# SCH1.net
KiCad netlist of a schematic drawn in EAGLE
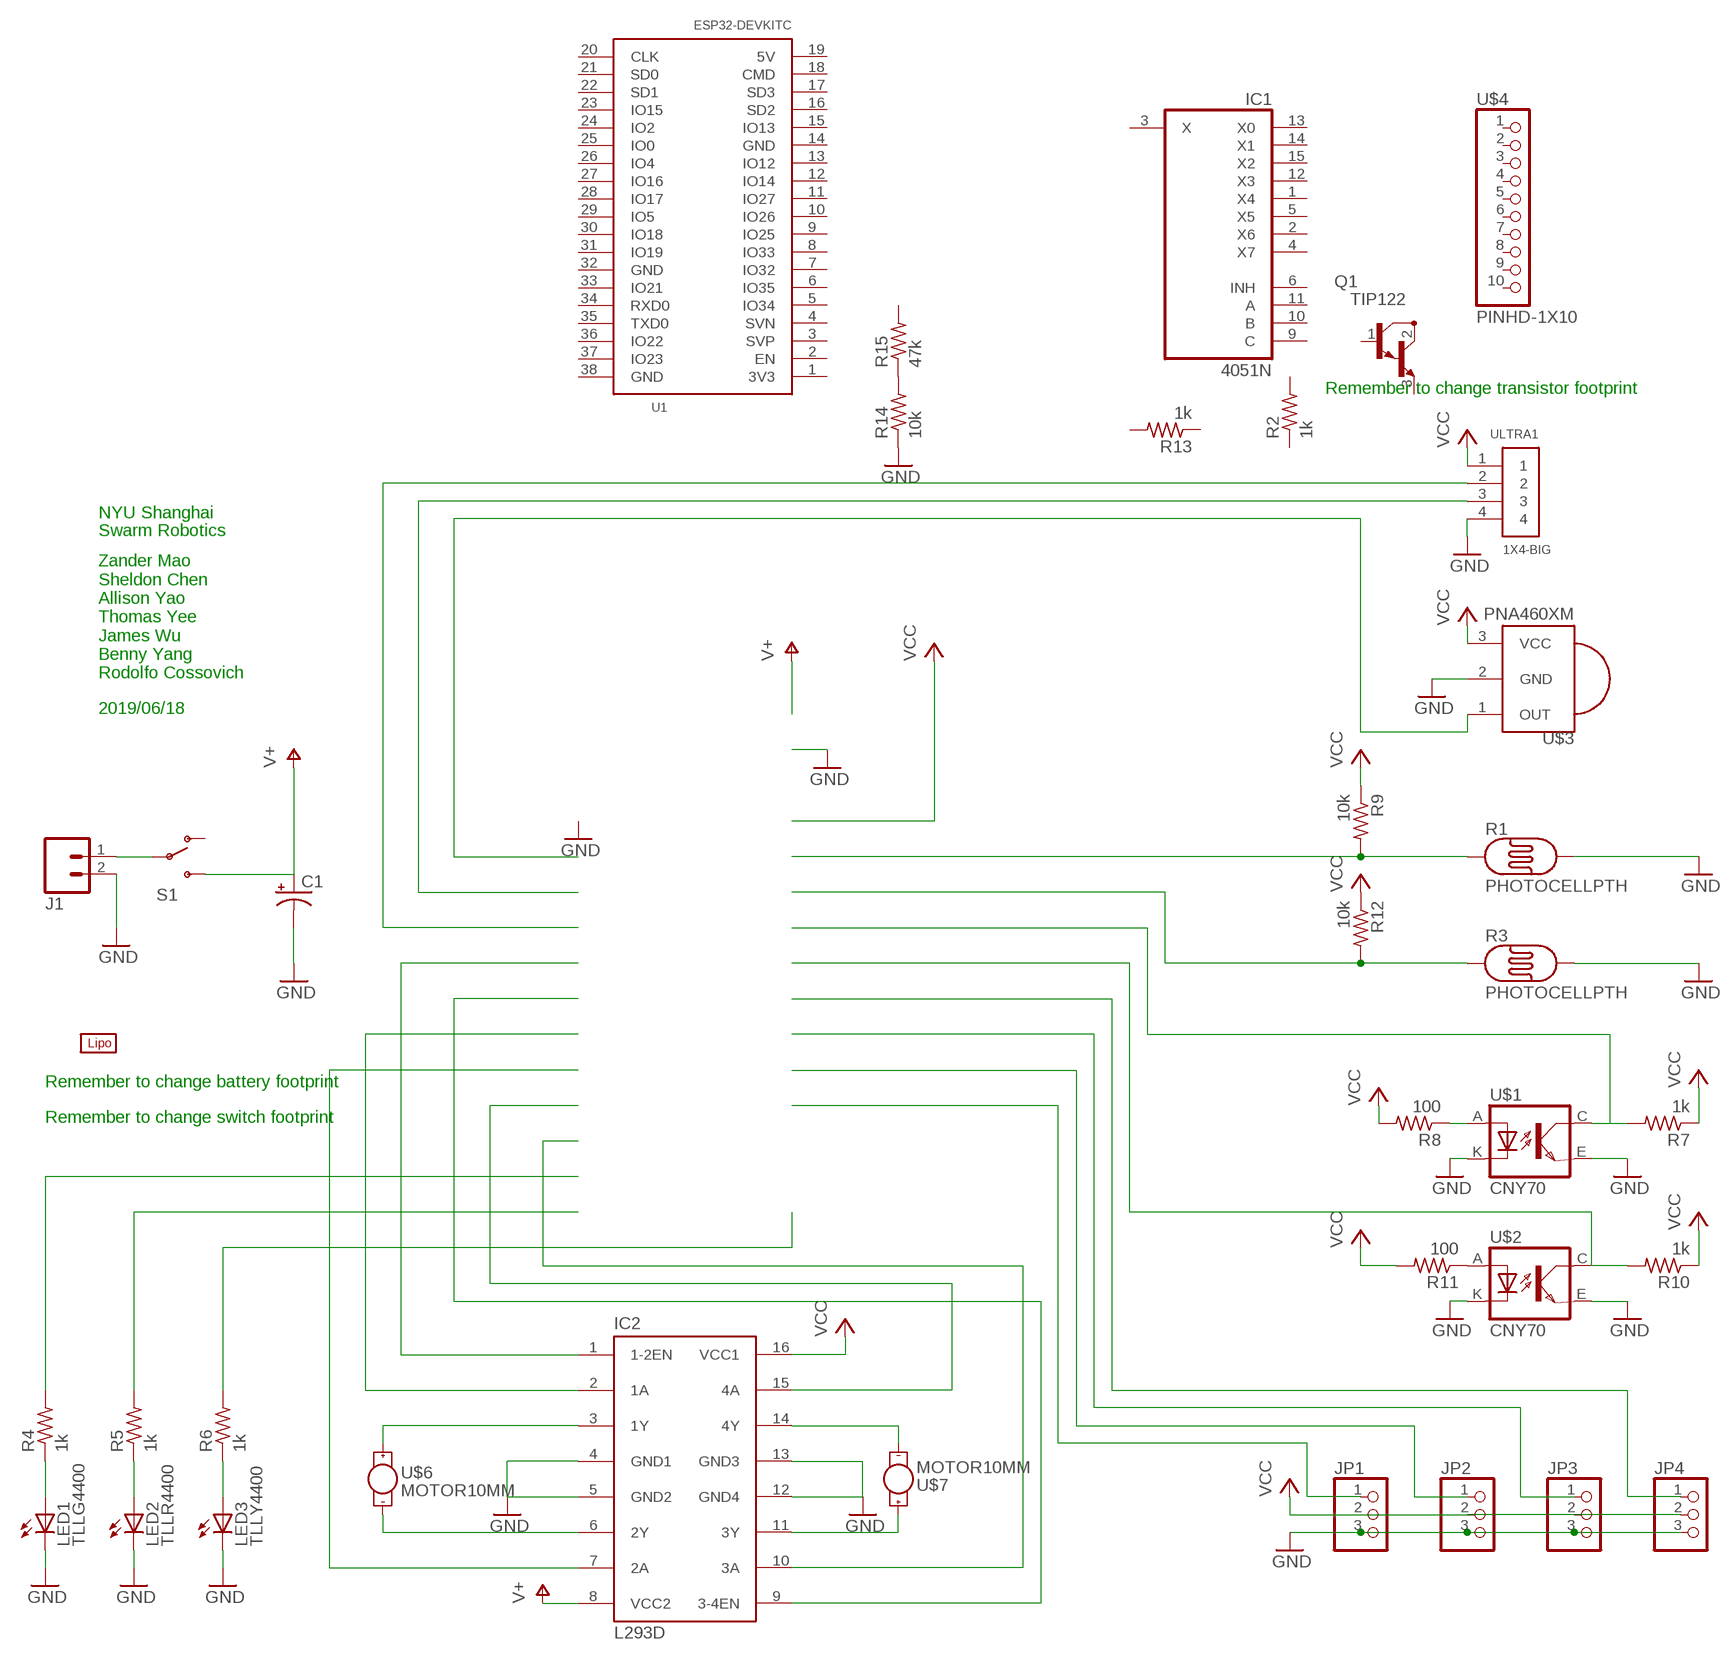
[diagram p0: schematic, sheet 1]

(export (version "E")
  (design (tool "Eeschema 10.0.6"))
  (components
    (comp (ref "C1")
      (value "CPOL-USE10-20")
      (footprint "eagle-import:EB20D")
      (libsource (lib "eagle-import") (part "CPOL-USE10-20"))
    )
    (comp (ref "IC1")
      (value "4051N")
      (footprint "eagle-import:DIL16")
      (libsource (lib "eagle-import") (part "4051N"))
    )
    (comp (ref "IC2")
      (value "L293D")
      (footprint "eagle-import:DIL16")
      (libsource (lib "eagle-import") (part "L293D"))
    )
    (comp (ref "J1")
      (value "M02-JST-2-PTH-NO_SILK")
      (footprint "eagle-import:JST-2-PTH-NS")
      (libsource (lib "eagle-import") (part "M02-JST-2-PTH-NO_SILK"))
    )
    (comp (ref "JP1")
      (value "PINHD-1X3")
      (footprint "eagle-import:1X03")
      (libsource (lib "eagle-import") (part "PINHD-1X3"))
    )
    (comp (ref "JP2")
      (value "PINHD-1X3")
      (footprint "eagle-import:1X03")
      (libsource (lib "eagle-import") (part "PINHD-1X3"))
    )
    (comp (ref "JP3")
      (value "PINHD-1X3")
      (footprint "eagle-import:1X03")
      (libsource (lib "eagle-import") (part "PINHD-1X3"))
    )
    (comp (ref "JP4")
      (value "PINHD-1X3")
      (footprint "eagle-import:1X03")
      (libsource (lib "eagle-import") (part "PINHD-1X3"))
    )
    (comp (ref "LED1")
      (value "TLLG4400")
      (footprint "eagle-import:LED3MM")
      (fields (field (name "MF") "VISHAY SEMICONDUCTOR"))
      (libsource (lib "eagle-import") (part "TLLG4400"))
    )
    (comp (ref "LED2")
      (value "TLLR4400")
      (footprint "eagle-import:LED3MM")
      (fields (field (name "MF") "VISHAY SEMICONDUCTOR"))
      (libsource (lib "eagle-import") (part "TLLR4400"))
    )
    (comp (ref "LED3")
      (value "TLLY4400")
      (footprint "eagle-import:LED3MM")
      (fields (field (name "MF") "VISHAY SEMICONDUCTOR"))
      (libsource (lib "eagle-import") (part "TLLY4400"))
    )
    (comp (ref "Q1")
      (value "TIP122")
      (footprint "eagle-import:TO220")
      (libsource (lib "eagle-import") (part "TIP122"))
    )
    (comp (ref "R1")
      (value "PHOTOCELLPTH")
      (footprint "eagle-import:PHOTOCELL")
      (libsource (lib "eagle-import") (part "PHOTOCELLPTH"))
    )
    (comp (ref "R2")
      (value "1k")
      (footprint "eagle-import:0207_12")
      (libsource (lib "eagle-import") (part "R-US_0207/12"))
    )
    (comp (ref "R3")
      (value "PHOTOCELLPTH")
      (footprint "eagle-import:PHOTOCELL")
      (libsource (lib "eagle-import") (part "PHOTOCELLPTH"))
    )
    (comp (ref "R4")
      (value "1k")
      (footprint "eagle-import:0207_12")
      (libsource (lib "eagle-import") (part "R-US_0207/12"))
    )
    (comp (ref "R5")
      (value "1k")
      (footprint "eagle-import:0207_12")
      (libsource (lib "eagle-import") (part "R-US_0207/12"))
    )
    (comp (ref "R6")
      (value "1k")
      (footprint "eagle-import:0207_12")
      (libsource (lib "eagle-import") (part "R-US_0207/12"))
    )
    (comp (ref "R7")
      (value "1k")
      (footprint "eagle-import:0207_12")
      (libsource (lib "eagle-import") (part "R-US_0207/12"))
    )
    (comp (ref "R8")
      (value "100")
      (footprint "eagle-import:0207_12")
      (libsource (lib "eagle-import") (part "R-US_0207/12"))
    )
    (comp (ref "R9")
      (value "10k")
      (footprint "eagle-import:0207_12")
      (libsource (lib "eagle-import") (part "R-US_0207/12"))
    )
    (comp (ref "R10")
      (value "1k")
      (footprint "eagle-import:0207_12")
      (libsource (lib "eagle-import") (part "R-US_0207/12"))
    )
    (comp (ref "R11")
      (value "100")
      (footprint "eagle-import:0207_12")
      (libsource (lib "eagle-import") (part "R-US_0207/12"))
    )
    (comp (ref "R12")
      (value "10k")
      (footprint "eagle-import:0207_12")
      (libsource (lib "eagle-import") (part "R-US_0207/12"))
    )
    (comp (ref "R13")
      (value "1k")
      (footprint "eagle-import:0207_12")
      (libsource (lib "eagle-import") (part "R-US_0207/12"))
    )
    (comp (ref "R14")
      (value "10k")
      (footprint "eagle-import:0207_12")
      (libsource (lib "eagle-import") (part "R-US_0207/12"))
    )
    (comp (ref "R15")
      (value "47k")
      (footprint "eagle-import:0207_12")
      (libsource (lib "eagle-import") (part "R-US_0207/12"))
    )
    (comp (ref "S1")
      (value "SWITCH-SPDTPTH2")
      (footprint "eagle-import:SWITCHE-DPDT")
      (libsource (lib "eagle-import") (part "SWITCH-SPDTPTH2"))
    )
    (comp (ref "U$1")
      (value "CNY70")
      (footprint "eagle-import:4")
      (libsource (lib "eagle-import") (part "CNY70"))
    )
    (comp (ref "U$2")
      (value "CNY70")
      (footprint "eagle-import:4")
      (libsource (lib "eagle-import") (part "CNY70"))
    )
    (comp (ref "U$3")
      (value "PNA460XM")
      (footprint "eagle-import:PNA460XM")
      (libsource (lib "eagle-import") (part "PNA460XM"))
    )
    (comp (ref "U$4")
      (value "PINHD-1X10")
      (footprint "eagle-import:1X10-BIG")
      (libsource (lib "eagle-import") (part "PINHD-1X10"))
    )
    (comp (ref "U$5")
      (value "LIPO-OUTLINE2000")
      (footprint "eagle-import:LIPO-2000")
      (libsource (lib "eagle-import") (part "LIPO-OUTLINE2000"))
    )
    (comp (ref "U$6")
      (value "MOTOR10MM")
      (footprint "eagle-import:VIBE-MOTOR-10MM")
      (libsource (lib "eagle-import") (part "MOTOR10MM"))
    )
    (comp (ref "U$7")
      (value "MOTOR10MM")
      (footprint "eagle-import:VIBE-MOTOR-10MM")
      (libsource (lib "eagle-import") (part "MOTOR10MM"))
    )
    (comp (ref "U1")
      (value "ESP32DEVKITC")
      (footprint "eagle-import:ESP32-DEVKITC")
      (libsource (lib "eagle-import") (part "ESP32DEVKITC"))
    )
    (comp (ref "ULTRA1")
      (value "1X4-BIG")
      (footprint "eagle-import:1X04-BIG")
      (libsource (lib "eagle-import") (part "1X4-BIG"))
    )
  )
  (nets
    (net (code "1") (name "GND") (class "Default")
      (node (ref "C1") (pin "-") (pinfunction "-_-") (pintype "passive"))
      (node (ref "IC2") (pin "12") (pinfunction "GND4_12") (pintype "power_in"))
      (node (ref "IC2") (pin "13") (pinfunction "GND3_13") (pintype "power_in"))
      (node (ref "IC2") (pin "4") (pinfunction "GND1_4") (pintype "power_in"))
      (node (ref "IC2") (pin "5") (pinfunction "GND2_5") (pintype "power_in"))
      (node (ref "J1") (pin "2") (pinfunction "2_2") (pintype "passive"))
      (node (ref "JP1") (pin "3") (pinfunction "3_3") (pintype "passive"))
      (node (ref "JP2") (pin "3") (pinfunction "3_3") (pintype "passive"))
      (node (ref "JP3") (pin "3") (pinfunction "3_3") (pintype "passive"))
      (node (ref "JP4") (pin "3") (pinfunction "3_3") (pintype "passive"))
      (node (ref "LED1") (pin "K") (pinfunction "C_K") (pintype "passive"))
      (node (ref "LED2") (pin "K") (pinfunction "C_K") (pintype "passive"))
      (node (ref "LED3") (pin "K") (pinfunction "C_K") (pintype "passive"))
      (node (ref "R1") (pin "2") (pinfunction "P$2_2") (pintype "bidirectional"))
      (node (ref "R14") (pin "1") (pinfunction "1_1") (pintype "passive"))
      (node (ref "R3") (pin "2") (pinfunction "P$2_2") (pintype "bidirectional"))
      (node (ref "U$1") (pin "E") (pinfunction "EMI_E") (pintype "passive"))
      (node (ref "U$1") (pin "K") (pinfunction "C_K") (pintype "passive"))
      (node (ref "U$2") (pin "E") (pinfunction "EMI_E") (pintype "passive"))
      (node (ref "U$2") (pin "K") (pinfunction "C_K") (pintype "passive"))
      (node (ref "U$3") (pin "2") (pinfunction "GND_2") (pintype "power_in"))
      (node (ref "ULTRA1") (pin "4") (pinfunction "4_4") (pintype "bidirectional"))
    )
    (net (code "2") (name "Net-(IC2-1Y)") (class "Default")
      (node (ref "IC2") (pin "3") (pinfunction "1Y_3") (pintype "output"))
      (node (ref "U$6") (pin "+") (pinfunction "+_+") (pintype "bidirectional"))
    )
    (net (code "3") (name "Net-(IC2-2Y)") (class "Default")
      (node (ref "IC2") (pin "6") (pinfunction "2Y_6") (pintype "output"))
      (node (ref "U$6") (pin "-") (pinfunction "-_-") (pintype "bidirectional"))
    )
    (net (code "4") (name "Net-(IC2-3Y)") (class "Default")
      (node (ref "IC2") (pin "11") (pinfunction "3Y_11") (pintype "output"))
      (node (ref "U$7") (pin "+") (pinfunction "+_+") (pintype "bidirectional"))
    )
    (net (code "5") (name "Net-(IC2-4Y)") (class "Default")
      (node (ref "IC2") (pin "14") (pinfunction "4Y_14") (pintype "output"))
      (node (ref "U$7") (pin "-") (pinfunction "-_-") (pintype "bidirectional"))
    )
    (net (code "6") (name "Net-(LED1-PadA)") (class "Default")
      (node (ref "LED1") (pin "A") (pinfunction "A_A") (pintype "passive"))
      (node (ref "R4") (pin "1") (pinfunction "1_1") (pintype "passive"))
    )
    (net (code "7") (name "Net-(LED2-PadA)") (class "Default")
      (node (ref "LED2") (pin "A") (pinfunction "A_A") (pintype "passive"))
      (node (ref "R5") (pin "1") (pinfunction "1_1") (pintype "passive"))
    )
    (net (code "8") (name "Net-(LED3-PadA)") (class "Default")
      (node (ref "LED3") (pin "A") (pinfunction "A_A") (pintype "passive"))
      (node (ref "R6") (pin "1") (pinfunction "1_1") (pintype "passive"))
    )
    (net (code "9") (name "Net-(R1-P$1)") (class "Default")
      (node (ref "R1") (pin "1") (pinfunction "P$1_1") (pintype "bidirectional"))
      (node (ref "R9") (pin "2") (pinfunction "2_2") (pintype "passive"))
    )
    (net (code "10") (name "Net-(R3-P$1)") (class "Default")
      (node (ref "R12") (pin "2") (pinfunction "2_2") (pintype "passive"))
      (node (ref "R3") (pin "1") (pinfunction "P$1_1") (pintype "bidirectional"))
    )
    (net (code "11") (name "Net-(R8-Pad1)") (class "Default")
      (node (ref "R8") (pin "1") (pinfunction "1_1") (pintype "passive"))
      (node (ref "U$1") (pin "A") (pinfunction "A_A") (pintype "passive"))
    )
    (net (code "12") (name "Net-(R11-Pad1)") (class "Default")
      (node (ref "R11") (pin "1") (pinfunction "1_1") (pintype "passive"))
      (node (ref "U$2") (pin "A") (pinfunction "A_A") (pintype "passive"))
    )
    (net (code "13") (name "Net-(R14-Pad2)") (class "Default")
      (node (ref "R14") (pin "2") (pinfunction "2_2") (pintype "passive"))
      (node (ref "R15") (pin "1") (pinfunction "1_1") (pintype "passive"))
    )
    (net (code "14") (name "Net-(S1-P)") (class "Default")
      (node (ref "J1") (pin "1") (pinfunction "1_1") (pintype "passive"))
      (node (ref "S1") (pin "2") (pinfunction "P_2") (pintype "passive"))
    )
    (net (code "15") (name "Net-(U$1-COL)") (class "Default")
      (node (ref "R7") (pin "2") (pinfunction "2_2") (pintype "passive"))
      (node (ref "U$1") (pin "C") (pinfunction "COL_C") (pintype "passive"))
    )
    (net (code "16") (name "Net-(U$2-COL)") (class "Default")
      (node (ref "R10") (pin "2") (pinfunction "2_2") (pintype "passive"))
      (node (ref "U$2") (pin "C") (pinfunction "COL_C") (pintype "passive"))
    )
    (net (code "17") (name "V+") (class "Default")
      (node (ref "C1") (pin "+") (pinfunction "+_+") (pintype "passive"))
      (node (ref "IC2") (pin "8") (pinfunction "VCC2_8") (pintype "power_in"))
      (node (ref "S1") (pin "3") (pinfunction "S_3") (pintype "passive"))
    )
    (net (code "18") (name "VCC") (class "Default")
      (node (ref "IC2") (pin "16") (pinfunction "VCC1_16") (pintype "power_in"))
      (node (ref "JP1") (pin "2") (pinfunction "2_2") (pintype "passive"))
      (node (ref "JP2") (pin "2") (pinfunction "2_2") (pintype "passive"))
      (node (ref "JP3") (pin "2") (pinfunction "2_2") (pintype "passive"))
      (node (ref "JP4") (pin "2") (pinfunction "2_2") (pintype "passive"))
      (node (ref "R10") (pin "1") (pinfunction "1_1") (pintype "passive"))
      (node (ref "R11") (pin "2") (pinfunction "2_2") (pintype "passive"))
      (node (ref "R12") (pin "1") (pinfunction "1_1") (pintype "passive"))
      (node (ref "R7") (pin "1") (pinfunction "1_1") (pintype "passive"))
      (node (ref "R8") (pin "2") (pinfunction "2_2") (pintype "passive"))
      (node (ref "R9") (pin "1") (pinfunction "1_1") (pintype "passive"))
      (node (ref "U$3") (pin "3") (pinfunction "VCC_3") (pintype "power_in"))
      (node (ref "ULTRA1") (pin "1") (pinfunction "1_1") (pintype "bidirectional"))
    )
    (net (code "19") (name "unconnected-(IC1A-A-Pad11)") (class "Default")
      (node (ref "IC1") (pin "11") (pinfunction "A_11") (pintype "input"))
    )
    (net (code "20") (name "unconnected-(IC1A-B-Pad10)") (class "Default")
      (node (ref "IC1") (pin "10") (pinfunction "B_10") (pintype "input"))
    )
    (net (code "21") (name "unconnected-(IC1A-C-Pad9)") (class "Default")
      (node (ref "IC1") (pin "9") (pinfunction "C_9") (pintype "input"))
    )
    (net (code "22") (name "unconnected-(IC1A-INH-Pad6)") (class "Default")
      (node (ref "IC1") (pin "6") (pinfunction "INH_6") (pintype "input"))
    )
    (net (code "23") (name "unconnected-(IC1A-X-Pad3)") (class "Default")
      (node (ref "IC1") (pin "3") (pinfunction "X_3") (pintype "bidirectional"))
    )
    (net (code "24") (name "unconnected-(IC1A-X0-Pad13)") (class "Default")
      (node (ref "IC1") (pin "13") (pinfunction "X0_13") (pintype "bidirectional"))
    )
    (net (code "25") (name "unconnected-(IC1A-X1-Pad14)") (class "Default")
      (node (ref "IC1") (pin "14") (pinfunction "X1_14") (pintype "bidirectional"))
    )
    (net (code "26") (name "unconnected-(IC1A-X2-Pad15)") (class "Default")
      (node (ref "IC1") (pin "15") (pinfunction "X2_15") (pintype "bidirectional"))
    )
    (net (code "27") (name "unconnected-(IC1A-X3-Pad12)") (class "Default")
      (node (ref "IC1") (pin "12") (pinfunction "X3_12") (pintype "bidirectional"))
    )
    (net (code "28") (name "unconnected-(IC1A-X4-Pad1)") (class "Default")
      (node (ref "IC1") (pin "1") (pinfunction "X4_1") (pintype "bidirectional"))
    )
    (net (code "29") (name "unconnected-(IC1A-X5-Pad5)") (class "Default")
      (node (ref "IC1") (pin "5") (pinfunction "X5_5") (pintype "bidirectional"))
    )
    (net (code "30") (name "unconnected-(IC1A-X6-Pad2)") (class "Default")
      (node (ref "IC1") (pin "2") (pinfunction "X6_2") (pintype "bidirectional"))
    )
    (net (code "31") (name "unconnected-(IC1A-X7-Pad4)") (class "Default")
      (node (ref "IC1") (pin "4") (pinfunction "X7_4") (pintype "bidirectional"))
    )
    (net (code "32") (name "unconnected-(IC2-1-2EN-Pad1)") (class "Default")
      (node (ref "IC2") (pin "1") (pinfunction "1-2EN_1") (pintype "input"))
    )
    (net (code "33") (name "unconnected-(IC2-1A-Pad2)") (class "Default")
      (node (ref "IC2") (pin "2") (pinfunction "1A_2") (pintype "input"))
    )
    (net (code "34") (name "unconnected-(IC2-2A-Pad7)") (class "Default")
      (node (ref "IC2") (pin "7") (pinfunction "2A_7") (pintype "input"))
    )
    (net (code "35") (name "unconnected-(IC2-3-4EN-Pad9)") (class "Default")
      (node (ref "IC2") (pin "9") (pinfunction "3-4EN_9") (pintype "input"))
    )
    (net (code "36") (name "unconnected-(IC2-3A-Pad10)") (class "Default")
      (node (ref "IC2") (pin "10") (pinfunction "3A_10") (pintype "input"))
    )
    (net (code "37") (name "unconnected-(IC2-4A-Pad15)") (class "Default")
      (node (ref "IC2") (pin "15") (pinfunction "4A_15") (pintype "input"))
    )
    (net (code "38") (name "unconnected-(JP1-Pad1)") (class "Default")
      (node (ref "JP1") (pin "1") (pinfunction "1_1") (pintype "passive"))
    )
    (net (code "39") (name "unconnected-(JP2-Pad1)") (class "Default")
      (node (ref "JP2") (pin "1") (pinfunction "1_1") (pintype "passive"))
    )
    (net (code "40") (name "unconnected-(JP3-Pad1)") (class "Default")
      (node (ref "JP3") (pin "1") (pinfunction "1_1") (pintype "passive"))
    )
    (net (code "41") (name "unconnected-(JP4-Pad1)") (class "Default")
      (node (ref "JP4") (pin "1") (pinfunction "1_1") (pintype "passive"))
    )
    (net (code "42") (name "unconnected-(Q1-B-Pad1)") (class "Default")
      (node (ref "Q1") (pin "1") (pinfunction "B_1") (pintype "passive"))
    )
    (net (code "43") (name "unconnected-(Q1-C-Pad2)") (class "Default")
      (node (ref "Q1") (pin "2") (pinfunction "C_2") (pintype "passive"))
    )
    (net (code "44") (name "unconnected-(Q1-E-Pad3)") (class "Default")
      (node (ref "Q1") (pin "3") (pinfunction "E_3") (pintype "passive"))
    )
    (net (code "45") (name "unconnected-(R2-Pad1)") (class "Default")
      (node (ref "R2") (pin "1") (pinfunction "1_1") (pintype "passive"))
    )
    (net (code "46") (name "unconnected-(R2-Pad2)") (class "Default")
      (node (ref "R2") (pin "2") (pinfunction "2_2") (pintype "passive"))
    )
    (net (code "47") (name "unconnected-(R4-Pad2)") (class "Default")
      (node (ref "R4") (pin "2") (pinfunction "2_2") (pintype "passive"))
    )
    (net (code "48") (name "unconnected-(R5-Pad2)") (class "Default")
      (node (ref "R5") (pin "2") (pinfunction "2_2") (pintype "passive"))
    )
    (net (code "49") (name "unconnected-(R6-Pad2)") (class "Default")
      (node (ref "R6") (pin "2") (pinfunction "2_2") (pintype "passive"))
    )
    (net (code "50") (name "unconnected-(R13-Pad1)") (class "Default")
      (node (ref "R13") (pin "1") (pinfunction "1_1") (pintype "passive"))
    )
    (net (code "51") (name "unconnected-(R13-Pad2)") (class "Default")
      (node (ref "R13") (pin "2") (pinfunction "2_2") (pintype "passive"))
    )
    (net (code "52") (name "unconnected-(R15-Pad2)") (class "Default")
      (node (ref "R15") (pin "2") (pinfunction "2_2") (pintype "passive"))
    )
    (net (code "53") (name "unconnected-(S1-O-Pad1)") (class "Default")
      (node (ref "S1") (pin "1") (pinfunction "O_1") (pintype "passive"))
    )
    (net (code "54") (name "unconnected-(U$3-OUT-Pad1)") (class "Default")
      (node (ref "U$3") (pin "1") (pinfunction "OUT_1") (pintype "output"))
    )
    (net (code "55") (name "unconnected-(U$4-Pad1)") (class "Default")
      (node (ref "U$4") (pin "1") (pinfunction "1_1") (pintype "passive"))
    )
    (net (code "56") (name "unconnected-(U$4-Pad2)") (class "Default")
      (node (ref "U$4") (pin "2") (pinfunction "2_2") (pintype "passive"))
    )
    (net (code "57") (name "unconnected-(U$4-Pad3)") (class "Default")
      (node (ref "U$4") (pin "3") (pinfunction "3_3") (pintype "passive"))
    )
    (net (code "58") (name "unconnected-(U$4-Pad4)") (class "Default")
      (node (ref "U$4") (pin "4") (pinfunction "4_4") (pintype "passive"))
    )
    (net (code "59") (name "unconnected-(U$4-Pad5)") (class "Default")
      (node (ref "U$4") (pin "5") (pinfunction "5_5") (pintype "passive"))
    )
    (net (code "60") (name "unconnected-(U$4-Pad6)") (class "Default")
      (node (ref "U$4") (pin "6") (pinfunction "6_6") (pintype "passive"))
    )
    (net (code "61") (name "unconnected-(U$4-Pad7)") (class "Default")
      (node (ref "U$4") (pin "7") (pinfunction "7_7") (pintype "passive"))
    )
    (net (code "62") (name "unconnected-(U$4-Pad8)") (class "Default")
      (node (ref "U$4") (pin "8") (pinfunction "8_8") (pintype "passive"))
    )
    (net (code "63") (name "unconnected-(U$4-Pad9)") (class "Default")
      (node (ref "U$4") (pin "9") (pinfunction "9_9") (pintype "passive"))
    )
    (net (code "64") (name "unconnected-(U$4-Pad10)") (class "Default")
      (node (ref "U$4") (pin "10") (pinfunction "10_10") (pintype "passive"))
    )
    (net (code "65") (name "unconnected-(U1-3V3-Pad1)") (class "Default")
      (node (ref "U1") (pin "1") (pinfunction "3V3_1") (pintype "bidirectional"))
    )
    (net (code "66") (name "unconnected-(U1-5V-Pad19)") (class "Default")
      (node (ref "U1") (pin "19") (pinfunction "5V_19") (pintype "bidirectional"))
    )
    (net (code "67") (name "unconnected-(U1-CLK-Pad20)") (class "Default")
      (node (ref "U1") (pin "20") (pinfunction "CLK_20") (pintype "bidirectional"))
    )
    (net (code "68") (name "unconnected-(U1-CMD-Pad18)") (class "Default")
      (node (ref "U1") (pin "18") (pinfunction "CMD_18") (pintype "bidirectional"))
    )
    (net (code "69") (name "unconnected-(U1-EN-Pad2)") (class "Default")
      (node (ref "U1") (pin "2") (pinfunction "EN_2") (pintype "bidirectional"))
    )
    (net (code "70") (name "unconnected-(U1-GND-Pad14)") (class "Default")
      (node (ref "U1") (pin "14") (pinfunction "GND_14") (pintype "bidirectional"))
    )
    (net (code "71") (name "unconnected-(U1-GND-Pad32)") (class "Default")
      (node (ref "U1") (pin "32") (pinfunction "GND_32") (pintype "bidirectional"))
    )
    (net (code "72") (name "unconnected-(U1-GND-Pad38)") (class "Default")
      (node (ref "U1") (pin "38") (pinfunction "GND_38") (pintype "bidirectional"))
    )
    (net (code "73") (name "unconnected-(U1-IO0-Pad25)") (class "Default")
      (node (ref "U1") (pin "25") (pinfunction "IO0_25") (pintype "bidirectional"))
    )
    (net (code "74") (name "unconnected-(U1-IO2-Pad24)") (class "Default")
      (node (ref "U1") (pin "24") (pinfunction "IO2_24") (pintype "bidirectional"))
    )
    (net (code "75") (name "unconnected-(U1-IO4-Pad26)") (class "Default")
      (node (ref "U1") (pin "26") (pinfunction "IO4_26") (pintype "bidirectional"))
    )
    (net (code "76") (name "unconnected-(U1-IO5-Pad29)") (class "Default")
      (node (ref "U1") (pin "29") (pinfunction "IO5_29") (pintype "bidirectional"))
    )
    (net (code "77") (name "unconnected-(U1-IO12-Pad13)") (class "Default")
      (node (ref "U1") (pin "13") (pinfunction "IO12_13") (pintype "bidirectional"))
    )
    (net (code "78") (name "unconnected-(U1-IO13-Pad15)") (class "Default")
      (node (ref "U1") (pin "15") (pinfunction "IO13_15") (pintype "bidirectional"))
    )
    (net (code "79") (name "unconnected-(U1-IO14-Pad12)") (class "Default")
      (node (ref "U1") (pin "12") (pinfunction "IO14_12") (pintype "bidirectional"))
    )
    (net (code "80") (name "unconnected-(U1-IO15-Pad23)") (class "Default")
      (node (ref "U1") (pin "23") (pinfunction "IO15_23") (pintype "bidirectional"))
    )
    (net (code "81") (name "unconnected-(U1-IO16-Pad27)") (class "Default")
      (node (ref "U1") (pin "27") (pinfunction "IO16_27") (pintype "bidirectional"))
    )
    (net (code "82") (name "unconnected-(U1-IO17-Pad28)") (class "Default")
      (node (ref "U1") (pin "28") (pinfunction "IO17_28") (pintype "bidirectional"))
    )
    (net (code "83") (name "unconnected-(U1-IO18-Pad30)") (class "Default")
      (node (ref "U1") (pin "30") (pinfunction "IO18_30") (pintype "bidirectional"))
    )
    (net (code "84") (name "unconnected-(U1-IO19-Pad31)") (class "Default")
      (node (ref "U1") (pin "31") (pinfunction "IO19_31") (pintype "bidirectional"))
    )
    (net (code "85") (name "unconnected-(U1-IO21-Pad33)") (class "Default")
      (node (ref "U1") (pin "33") (pinfunction "IO21_33") (pintype "bidirectional"))
    )
    (net (code "86") (name "unconnected-(U1-IO22-Pad36)") (class "Default")
      (node (ref "U1") (pin "36") (pinfunction "IO22_36") (pintype "bidirectional"))
    )
    (net (code "87") (name "unconnected-(U1-IO23-Pad37)") (class "Default")
      (node (ref "U1") (pin "37") (pinfunction "IO23_37") (pintype "bidirectional"))
    )
    (net (code "88") (name "unconnected-(U1-IO25-Pad9)") (class "Default")
      (node (ref "U1") (pin "9") (pinfunction "IO25_9") (pintype "bidirectional"))
    )
    (net (code "89") (name "unconnected-(U1-IO26-Pad10)") (class "Default")
      (node (ref "U1") (pin "10") (pinfunction "IO26_10") (pintype "bidirectional"))
    )
    (net (code "90") (name "unconnected-(U1-IO27-Pad11)") (class "Default")
      (node (ref "U1") (pin "11") (pinfunction "IO27_11") (pintype "bidirectional"))
    )
    (net (code "91") (name "unconnected-(U1-IO32-Pad7)") (class "Default")
      (node (ref "U1") (pin "7") (pinfunction "IO32_7") (pintype "bidirectional"))
    )
    (net (code "92") (name "unconnected-(U1-IO33-Pad8)") (class "Default")
      (node (ref "U1") (pin "8") (pinfunction "IO33_8") (pintype "bidirectional"))
    )
    (net (code "93") (name "unconnected-(U1-IO34-Pad5)") (class "Default")
      (node (ref "U1") (pin "5") (pinfunction "IO34_5") (pintype "bidirectional"))
    )
    (net (code "94") (name "unconnected-(U1-IO35-Pad6)") (class "Default")
      (node (ref "U1") (pin "6") (pinfunction "IO35_6") (pintype "bidirectional"))
    )
    (net (code "95") (name "unconnected-(U1-RXD0-Pad34)") (class "Default")
      (node (ref "U1") (pin "34") (pinfunction "RXD0_34") (pintype "bidirectional"))
    )
    (net (code "96") (name "unconnected-(U1-SD0-Pad21)") (class "Default")
      (node (ref "U1") (pin "21") (pinfunction "SD0_21") (pintype "bidirectional"))
    )
    (net (code "97") (name "unconnected-(U1-SD1-Pad22)") (class "Default")
      (node (ref "U1") (pin "22") (pinfunction "SD1_22") (pintype "bidirectional"))
    )
    (net (code "98") (name "unconnected-(U1-SD2-Pad16)") (class "Default")
      (node (ref "U1") (pin "16") (pinfunction "SD2_16") (pintype "bidirectional"))
    )
    (net (code "99") (name "unconnected-(U1-SD3-Pad17)") (class "Default")
      (node (ref "U1") (pin "17") (pinfunction "SD3_17") (pintype "bidirectional"))
    )
    (net (code "100") (name "unconnected-(U1-SVN-Pad4)") (class "Default")
      (node (ref "U1") (pin "4") (pinfunction "SVN_4") (pintype "bidirectional"))
    )
    (net (code "101") (name "unconnected-(U1-SVP-Pad3)") (class "Default")
      (node (ref "U1") (pin "3") (pinfunction "SVP_3") (pintype "bidirectional"))
    )
    (net (code "102") (name "unconnected-(U1-TXD0-Pad35)") (class "Default")
      (node (ref "U1") (pin "35") (pinfunction "TXD0_35") (pintype "bidirectional"))
    )
    (net (code "103") (name "unconnected-(ULTRA1-Pad2)") (class "Default")
      (node (ref "ULTRA1") (pin "2") (pinfunction "2_2") (pintype "bidirectional"))
    )
    (net (code "104") (name "unconnected-(ULTRA1-Pad3)") (class "Default")
      (node (ref "ULTRA1") (pin "3") (pinfunction "3_3") (pintype "bidirectional"))
    )
  )
)
